# 02-PSU-ps2-blueretro.net
KiCad netlist of a schematic drawn in Altium Designer
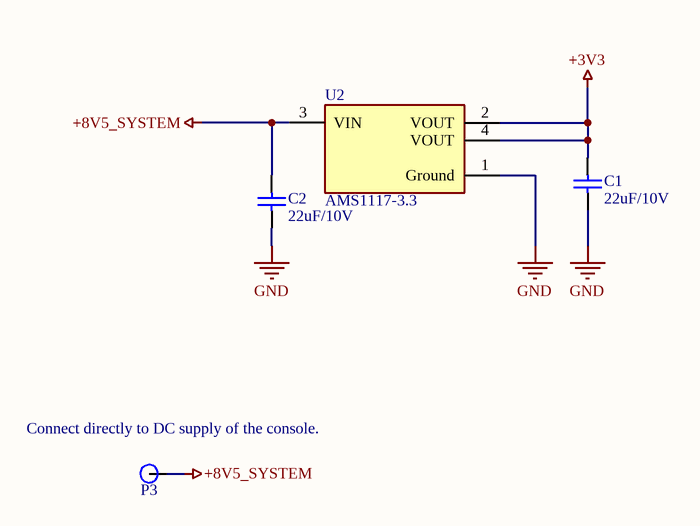
[diagram p0: 02-PSU-ps2-blueretro.SchDoc]

(export (version "E")
  (design (tool "Eeschema 10.0.6"))
  (components
    (comp (ref "C1")
      (value "22uF/10V")
      (footprint "cap_0603")
      (fields (field (name "Comment") "cap_0603"))
      (libsource (lib "mycomponents") (part "cap_0603"))
    )
    (comp (ref "C2")
      (value "22uF/10V")
      (footprint "cap_0603")
      (fields (field (name "Comment") "cap_0603"))
      (libsource (lib "mycomponents") (part "cap_0603"))
    )
    (comp (ref "P3")
      (value "Solder_Contact_2mm")
      (footprint "SINGLE_SOLDER_CON")
      (libsource (lib "mycomponents") (part "Solder_Contact_2mm"))
    )
    (comp (ref "U2")
      (value "AMS1117-3.3")
      (footprint "FP-AMS1117-IPC_C")
      (description "LDO Voltage Regulators 1A, 3.3V")
      (fields
        (field (name "OCTOPART") "https://octopart.com/ams1117-3.3-advanced+monolithic+systems-25899300")
        (field (name "MANUFACTURER") "Advanced Monolithic Systems")
      )
      (libsource (lib "Altium Content Vault") (part "8bdbb5f8e77002000e30dd2845d0354"))
    )
  )
  (nets
    (net (code "1") (name "+3V3") (class "Default")
      (node (ref "C1") (pin "2") (pinfunction "2_2") (pintype "passive"))
      (node (ref "U2") (pin "2") (pinfunction "VOUT_2") (pintype "passive"))
      (node (ref "U2") (pin "4") (pinfunction "VOUT_4") (pintype "passive"))
    )
    (net (code "2") (name "+8V5_SYSTEM") (class "Default")
      (node (ref "C2") (pin "2") (pinfunction "2_2") (pintype "passive"))
      (node (ref "P3") (pin "1") (pinfunction "1_1") (pintype "passive"))
      (node (ref "U2") (pin "3") (pinfunction "VIN_3") (pintype "power_in"))
    )
    (net (code "3") (name "GND") (class "Default")
      (node (ref "C1") (pin "1") (pinfunction "1_1") (pintype "passive"))
      (node (ref "C2") (pin "1") (pinfunction "1_1") (pintype "passive"))
      (node (ref "U2") (pin "1") (pinfunction "Ground_1") (pintype "power_in"))
    )
  )
)
